# Controller.net
KiCad netlist of a schematic drawn in Altium Designer
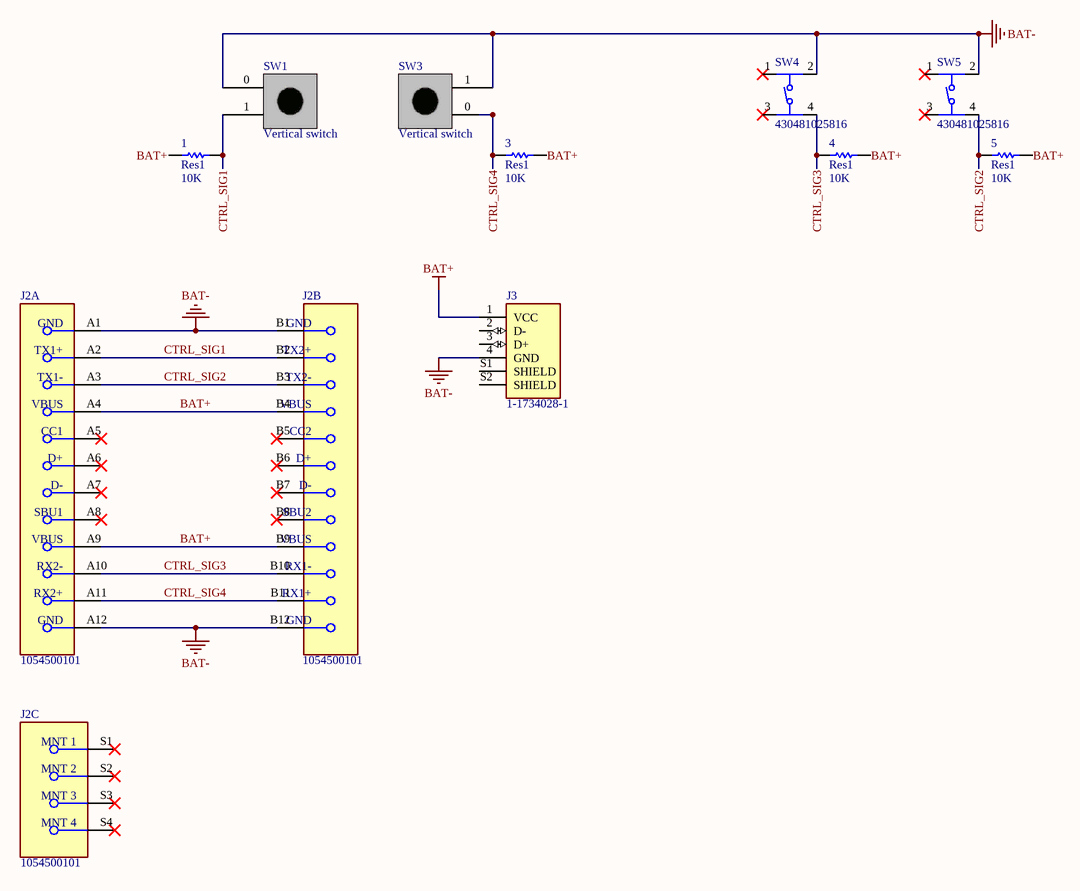
[diagram p0: Controller.SchDoc]

(export (version "E")
  (design (tool "Eeschema 10.0.6"))
  (components
    (comp (ref "1")
      (value "Res1")
      (footprint "6-0805_N")
      (description "C269531")
      (fields (field (name "ALTIUM_VALUE") "10K") (field (name "PUBLISHER") "Altium Limited"))
      (libsource (lib "Miscellaneous Devices") (part "Res1"))
    )
    (comp (ref "3")
      (value "Res1")
      (footprint "6-0805_N")
      (description "C269531")
      (fields (field (name "ALTIUM_VALUE") "10K") (field (name "PUBLISHER") "Altium Limited"))
      (libsource (lib "Miscellaneous Devices") (part "Res1"))
    )
    (comp (ref "4")
      (value "Res1")
      (footprint "6-0805_N")
      (description "C269531")
      (fields (field (name "ALTIUM_VALUE") "10K") (field (name "PUBLISHER") "Altium Limited"))
      (libsource (lib "Miscellaneous Devices") (part "Res1"))
    )
    (comp (ref "5")
      (value "Res1")
      (footprint "6-0805_N")
      (description "C269531")
      (fields (field (name "ALTIUM_VALUE") "10K") (field (name "PUBLISHER") "Altium Limited"))
      (libsource (lib "Miscellaneous Devices") (part "Res1"))
    )
    (comp (ref "J2")
      (value "1054500101")
      (footprint "USB_C_Receptacle_Amphenol_12401548E4-2A")
      (description "CONN RCP USB3.1 TYPEC 24P SMD RA")
      (fields
        (field (name "MANUFACTURER") "Molex")
        (field (name "OCTOPART") "https://octopart.com/105450-0101-molex-68082325")
      )
      (libsource (lib "") (part "9808b19ecaf079fb99eed69f0495cd0_1"))
    )
    (comp (ref "J3")
      (value "1-1734028-1")
      (footprint "TE_1-1734028-1")
      (description "Conn USB 2.0 Type A PL 4 POS Solder RA SMD 4 Terminal 1 Port T/R")
      (fields (field (name "MF") "{'manufacturer': u'TE Connectivity'}"))
      (libsource (lib "Brillz4Components") (part "1-1734028-1"))
    )
    (comp (ref "SW1")
      (value "Vertical switch")
      (footprint "Btn_Vert")
      (description "C294508")
      (libsource (lib "") (part "SWVERT_1"))
    )
    (comp (ref "SW3")
      (value "Vertical switch")
      (footprint "Btn_Vert")
      (description "C294508")
      (libsource (lib "Btn_Vert") (part "SWVERT"))
    )
    (comp (ref "SW4")
      (value "430481025816")
      (footprint "430481025816")
      (fields (field (name "MF") "{'manufacturer': u'Wurth Elektronik'}"))
      (libsource (lib "430481025816") (part "430481025816"))
    )
    (comp (ref "SW5")
      (value "430481025816")
      (footprint "430481025816")
      (fields (field (name "MF") "{'manufacturer': u'Wurth Elektronik'}"))
      (libsource (lib "430481025816") (part "430481025816"))
    )
  )
  (nets
    (net (code "1") (name "/CTRL_SIG1") (class "Default")
      (node (ref "1") (pin "1") (pinfunction "1_1") (pintype "passive"))
      (node (ref "J2") (pin "A2") (pinfunction "TX1+_A2") (pintype "passive"))
      (node (ref "J2") (pin "B2") (pinfunction "TX2+_B2") (pintype "passive"))
      (node (ref "SW1") (pin "1") (pintype "passive"))
    )
    (net (code "2") (name "/CTRL_SIG2") (class "Default")
      (node (ref "5") (pin "2") (pinfunction "2_2") (pintype "passive"))
      (node (ref "J2") (pin "A3") (pinfunction "TX1-_A3") (pintype "passive"))
      (node (ref "J2") (pin "B3") (pinfunction "TX2-_B3") (pintype "passive"))
      (node (ref "SW5") (pin "4") (pinfunction "4_4") (pintype "passive"))
    )
    (net (code "3") (name "/CTRL_SIG3") (class "Default")
      (node (ref "4") (pin "2") (pinfunction "2_2") (pintype "passive"))
      (node (ref "J2") (pin "A10") (pinfunction "RX2-_A10") (pintype "passive"))
      (node (ref "J2") (pin "B10") (pinfunction "RX1-_B10") (pintype "passive"))
      (node (ref "SW4") (pin "4") (pinfunction "4_4") (pintype "passive"))
    )
    (net (code "4") (name "/CTRL_SIG4") (class "Default")
      (node (ref "3") (pin "2") (pinfunction "2_2") (pintype "passive"))
      (node (ref "J2") (pin "A11") (pinfunction "RX2+_A11") (pintype "passive"))
      (node (ref "J2") (pin "B11") (pinfunction "RX1+_B11") (pintype "passive"))
      (node (ref "SW3") (pin "0") (pintype "passive"))
    )
    (net (code "5") (name "BAT+") (class "Default")
      (node (ref "1") (pin "2") (pinfunction "2_2") (pintype "passive"))
      (node (ref "3") (pin "1") (pinfunction "1_1") (pintype "passive"))
      (node (ref "4") (pin "1") (pinfunction "1_1") (pintype "passive"))
      (node (ref "5") (pin "1") (pinfunction "1_1") (pintype "passive"))
      (node (ref "J2") (pin "A4") (pinfunction "VBUS_A4") (pintype "passive"))
      (node (ref "J2") (pin "A9") (pinfunction "VBUS_A9") (pintype "passive"))
      (node (ref "J2") (pin "B4") (pinfunction "VBUS_B4") (pintype "passive"))
      (node (ref "J2") (pin "B9") (pinfunction "VBUS_B9") (pintype "passive"))
      (node (ref "J3") (pin "1") (pinfunction "VCC_1") (pintype "power_in"))
    )
    (net (code "6") (name "BAT-") (class "Default")
      (node (ref "J2") (pin "A1") (pinfunction "GND_A1") (pintype "passive"))
      (node (ref "J2") (pin "A12") (pinfunction "GND_A12") (pintype "passive"))
      (node (ref "J2") (pin "B1") (pinfunction "GND_B1") (pintype "passive"))
      (node (ref "J2") (pin "B12") (pinfunction "GND_B12") (pintype "passive"))
      (node (ref "J3") (pin "4") (pinfunction "GND_4") (pintype "power_in"))
      (node (ref "SW1") (pin "0") (pintype "passive"))
      (node (ref "SW3") (pin "1") (pintype "passive"))
      (node (ref "SW4") (pin "2") (pinfunction "2_2") (pintype "passive"))
      (node (ref "SW5") (pin "2") (pinfunction "2_2") (pintype "passive"))
    )
    (net (code "7") (name "unconnected-(J2A-CC1-PadA5)") (class "Default")
      (node (ref "J2") (pin "A5") (pinfunction "CC1_A5") (pintype "passive+no_connect"))
    )
    (net (code "8") (name "unconnected-(J2A-D+-PadA6)") (class "Default")
      (node (ref "J2") (pin "A6") (pinfunction "D+_A6") (pintype "passive+no_connect"))
    )
    (net (code "9") (name "unconnected-(J2A-D--PadA7)") (class "Default")
      (node (ref "J2") (pin "A7") (pinfunction "D-_A7") (pintype "passive+no_connect"))
    )
    (net (code "10") (name "unconnected-(J2A-SBU1-PadA8)") (class "Default")
      (node (ref "J2") (pin "A8") (pinfunction "SBU1_A8") (pintype "passive+no_connect"))
    )
    (net (code "11") (name "unconnected-(J2B-CC2-PadB5)") (class "Default")
      (node (ref "J2") (pin "B5") (pinfunction "CC2_B5") (pintype "passive+no_connect"))
    )
    (net (code "12") (name "unconnected-(J2B-D+-PadB6)") (class "Default")
      (node (ref "J2") (pin "B6") (pinfunction "D+_B6") (pintype "passive+no_connect"))
    )
    (net (code "13") (name "unconnected-(J2B-D--PadB7)") (class "Default")
      (node (ref "J2") (pin "B7") (pinfunction "D-_B7") (pintype "passive+no_connect"))
    )
    (net (code "14") (name "unconnected-(J2B-SBU2-PadB8)") (class "Default")
      (node (ref "J2") (pin "B8") (pinfunction "SBU2_B8") (pintype "passive+no_connect"))
    )
    (net (code "15") (name "unconnected-(J2C-MNT_1-PadS1)") (class "Default")
      (node (ref "J2") (pin "S1") (pinfunction "MNT_1_S1") (pintype "passive+no_connect"))
    )
    (net (code "16") (name "unconnected-(J2C-MNT_2-PadS2)") (class "Default")
      (node (ref "J2") (pin "S2") (pinfunction "MNT_2_S2") (pintype "passive+no_connect"))
    )
    (net (code "17") (name "unconnected-(J2C-MNT_3-PadS3)") (class "Default")
      (node (ref "J2") (pin "S3") (pinfunction "MNT_3_S3") (pintype "passive+no_connect"))
    )
    (net (code "18") (name "unconnected-(J2C-MNT_4-PadS4)") (class "Default")
      (node (ref "J2") (pin "S4") (pinfunction "MNT_4_S4") (pintype "passive+no_connect"))
    )
    (net (code "19") (name "unconnected-(J3-D+-Pad3)") (class "Default")
      (node (ref "J3") (pin "3") (pinfunction "D+_3") (pintype "bidirectional"))
    )
    (net (code "20") (name "unconnected-(J3-D--Pad2)") (class "Default")
      (node (ref "J3") (pin "2") (pinfunction "D-_2") (pintype "bidirectional"))
    )
    (net (code "21") (name "unconnected-(J3-SHIELD-PadS1)") (class "Default")
      (node (ref "J3") (pin "S1") (pinfunction "SHIELD_S1") (pintype "power_in"))
    )
    (net (code "22") (name "unconnected-(J3-SHIELD-PadS2)") (class "Default")
      (node (ref "J3") (pin "S2") (pinfunction "SHIELD_S2") (pintype "power_in"))
    )
    (net (code "23") (name "unconnected-(SW4-Pad1)") (class "Default")
      (node (ref "SW4") (pin "1") (pinfunction "1_1") (pintype "passive+no_connect"))
    )
    (net (code "24") (name "unconnected-(SW4-Pad3)") (class "Default")
      (node (ref "SW4") (pin "3") (pinfunction "3_3") (pintype "passive+no_connect"))
    )
    (net (code "25") (name "unconnected-(SW5-Pad1)") (class "Default")
      (node (ref "SW5") (pin "1") (pinfunction "1_1") (pintype "passive+no_connect"))
    )
    (net (code "26") (name "unconnected-(SW5-Pad3)") (class "Default")
      (node (ref "SW5") (pin "3") (pinfunction "3_3") (pintype "passive+no_connect"))
    )
  )
)
